# featherwing-interface.net
KiCad netlist of a schematic drawn in EAGLE
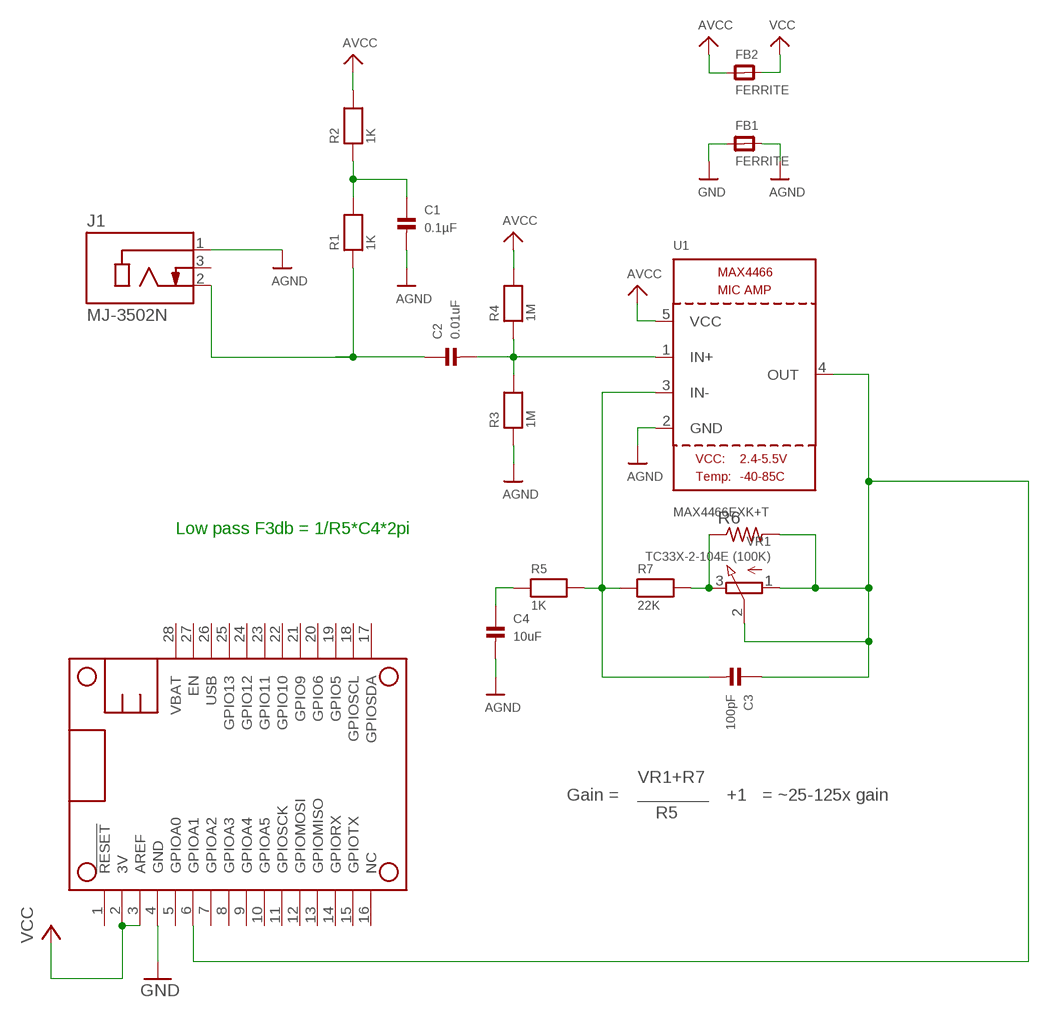
[diagram p0: schematic, sheet 1]

(export (version "E")
  (design (tool "Eeschema 10.0.6"))
  (components
    (comp (ref "C1")
      (value "0.1µF")
      (footprint "eagle-import:0805")
      (libsource (lib "eagle-import") (part "CAP_CERAMIC0805"))
    )
    (comp (ref "C2")
      (value "0.01uF")
      (footprint "eagle-import:0805")
      (libsource (lib "eagle-import") (part "CAP_CERAMIC0805"))
    )
    (comp (ref "C3")
      (value "100pF")
      (footprint "eagle-import:0805")
      (libsource (lib "eagle-import") (part "CAP_CERAMIC0805"))
    )
    (comp (ref "C4")
      (value "10uF")
      (footprint "eagle-import:0805")
      (libsource (lib "eagle-import") (part "CAP_CERAMIC0805"))
    )
    (comp (ref "FB1")
      (value "FERRITE")
      (footprint "eagle-import:0805")
      (libsource (lib "eagle-import") (part "FERRITE0805"))
    )
    (comp (ref "FB2")
      (value "FERRITE")
      (footprint "eagle-import:0805")
      (libsource (lib "eagle-import") (part "FERRITE0805"))
    )
    (comp (ref "J1")
      (value "MJ-3502N")
      (footprint "eagle-import:CUI_MJ-3502N")
      (fields (field (name "MANUFACTURER") "CUI INC"))
      (libsource (lib "eagle-import") (part "MJ-3502N"))
    )
    (comp (ref "MS1")
      (value "FEATHERWING")
      (footprint "eagle-import:FEATHERWING")
      (libsource (lib "eagle-import") (part "FEATHERWING"))
    )
    (comp (ref "R1")
      (value "1K")
      (footprint "eagle-import:0805")
      (libsource (lib "eagle-import") (part "RESISTOR0805"))
    )
    (comp (ref "R2")
      (value "1K")
      (footprint "eagle-import:0805")
      (libsource (lib "eagle-import") (part "RESISTOR0805"))
    )
    (comp (ref "R3")
      (value "1M")
      (footprint "eagle-import:0805")
      (libsource (lib "eagle-import") (part "RESISTOR0805"))
    )
    (comp (ref "R4")
      (value "1M")
      (footprint "eagle-import:0805")
      (libsource (lib "eagle-import") (part "RESISTOR0805"))
    )
    (comp (ref "R5")
      (value "1K")
      (footprint "eagle-import:0805")
      (libsource (lib "eagle-import") (part "RESISTOR0805"))
    )
    (comp (ref "R6")
      (value "R-US_0207/10")
      (footprint "eagle-import:0207_10")
      (libsource (lib "eagle-import") (part "R-US_0207/10"))
    )
    (comp (ref "R7")
      (value "22K")
      (footprint "eagle-import:0805")
      (libsource (lib "eagle-import") (part "RESISTOR0805"))
    )
    (comp (ref "U1")
      (value "MAX4466EXK+T")
      (footprint "eagle-import:SC70-5")
      (libsource (lib "eagle-import") (part "MAX4466{dblquote}{dblquote}"))
    )
    (comp (ref "VR1")
      (value "TC33X-2-104E (100K)")
      (footprint "eagle-import:TRIMPOT_BOURNS_TC33X-2")
      (libsource (lib "eagle-import") (part "TRIMPOTTC33X-2"))
    )
  )
  (nets
    (net (code "1") (name "/USB") (class "Default")
      (node (ref "MS1") (pin "26") (pinfunction "USB_26") (pintype "power_in"))
    )
    (net (code "2") (name "/VBAT") (class "Default")
      (node (ref "MS1") (pin "28") (pinfunction "VBAT_28") (pintype "power_in"))
    )
    (net (code "3") (name "AGND") (class "Default")
      (node (ref "C1") (pin "2") (pinfunction "P$2_2") (pintype "passive"))
      (node (ref "C4") (pin "2") (pinfunction "P$2_2") (pintype "passive"))
      (node (ref "FB1") (pin "2") (pinfunction "P$2_2") (pintype "passive"))
      (node (ref "J1") (pin "1") (pinfunction "1_1") (pintype "passive"))
      (node (ref "R3") (pin "1") (pinfunction "1_1") (pintype "passive"))
      (node (ref "U1") (pin "2") (pinfunction "GND_2") (pintype "bidirectional"))
    )
    (net (code "4") (name "AVCC") (class "Default")
      (node (ref "FB2") (pin "1") (pinfunction "P$1_1") (pintype "passive"))
      (node (ref "R2") (pin "2") (pinfunction "2_2") (pintype "passive"))
      (node (ref "R4") (pin "2") (pinfunction "2_2") (pintype "passive"))
      (node (ref "U1") (pin "5") (pinfunction "VCC_5") (pintype "bidirectional"))
    )
    (net (code "5") (name "GND") (class "Default")
      (node (ref "FB1") (pin "1") (pinfunction "P$1_1") (pintype "passive"))
      (node (ref "MS1") (pin "4") (pinfunction "GND_4") (pintype "power_in"))
    )
    (net (code "6") (name "Net-(C1-P$1)") (class "Default")
      (node (ref "C1") (pin "1") (pinfunction "P$1_1") (pintype "passive"))
      (node (ref "R1") (pin "2") (pinfunction "2_2") (pintype "passive"))
      (node (ref "R2") (pin "1") (pinfunction "1_1") (pintype "passive"))
    )
    (net (code "7") (name "Net-(C2-P$1)") (class "Default")
      (node (ref "C2") (pin "1") (pinfunction "P$1_1") (pintype "passive"))
      (node (ref "J1") (pin "2") (pinfunction "2_2") (pintype "passive"))
      (node (ref "R1") (pin "1") (pinfunction "1_1") (pintype "passive"))
    )
    (net (code "8") (name "Net-(C2-P$2)") (class "Default")
      (node (ref "C2") (pin "2") (pinfunction "P$2_2") (pintype "passive"))
      (node (ref "R3") (pin "2") (pinfunction "2_2") (pintype "passive"))
      (node (ref "R4") (pin "1") (pinfunction "1_1") (pintype "passive"))
      (node (ref "U1") (pin "1") (pinfunction "IN+_1") (pintype "bidirectional"))
    )
    (net (code "9") (name "Net-(C3-P$1)") (class "Default")
      (node (ref "C3") (pin "1") (pinfunction "P$1_1") (pintype "passive"))
      (node (ref "MS1") (pin "6") (pinfunction "GPIOA1_6") (pintype "bidirectional"))
      (node (ref "R6") (pin "2") (pinfunction "2_2") (pintype "passive"))
      (node (ref "U1") (pin "4") (pinfunction "OUT_4") (pintype "bidirectional"))
      (node (ref "VR1") (pin "1") (pinfunction "A_1") (pintype "passive"))
      (node (ref "VR1") (pin "2") (pinfunction "S_2") (pintype "passive"))
    )
    (net (code "10") (name "Net-(C3-P$2)") (class "Default")
      (node (ref "C3") (pin "2") (pinfunction "P$2_2") (pintype "passive"))
      (node (ref "R5") (pin "2") (pinfunction "2_2") (pintype "passive"))
      (node (ref "R7") (pin "1") (pinfunction "1_1") (pintype "passive"))
      (node (ref "U1") (pin "3") (pinfunction "IN-_3") (pintype "bidirectional"))
    )
    (net (code "11") (name "Net-(C4-P$1)") (class "Default")
      (node (ref "C4") (pin "1") (pinfunction "P$1_1") (pintype "passive"))
      (node (ref "R5") (pin "1") (pinfunction "1_1") (pintype "passive"))
    )
    (net (code "12") (name "Net-(VR1-E)") (class "Default")
      (node (ref "R6") (pin "1") (pinfunction "1_1") (pintype "passive"))
      (node (ref "R7") (pin "2") (pinfunction "2_2") (pintype "passive"))
      (node (ref "VR1") (pin "3") (pinfunction "E_3") (pintype "passive"))
    )
    (net (code "13") (name "VCC") (class "Default")
      (node (ref "FB2") (pin "2") (pinfunction "P$2_2") (pintype "passive"))
      (node (ref "MS1") (pin "2") (pinfunction "3V_2") (pintype "power_in"))
      (node (ref "MS1") (pin "3") (pinfunction "AREF_3") (pintype "passive"))
    )
    (net (code "14") (name "unconnected-(J1-Pad3)") (class "Default")
      (node (ref "J1") (pin "3") (pinfunction "3_3") (pintype "passive"))
    )
    (net (code "15") (name "unconnected-(MS1-EN-Pad27)") (class "Default")
      (node (ref "MS1") (pin "27") (pinfunction "EN_27") (pintype "passive"))
    )
    (net (code "16") (name "unconnected-(MS1-GPIO5-Pad19)") (class "Default")
      (node (ref "MS1") (pin "19") (pinfunction "GPIO5_19") (pintype "bidirectional"))
    )
    (net (code "17") (name "unconnected-(MS1-GPIO6-Pad20)") (class "Default")
      (node (ref "MS1") (pin "20") (pinfunction "GPIO6_20") (pintype "bidirectional"))
    )
    (net (code "18") (name "unconnected-(MS1-GPIO9-Pad21)") (class "Default")
      (node (ref "MS1") (pin "21") (pinfunction "GPIO9_21") (pintype "bidirectional"))
    )
    (net (code "19") (name "unconnected-(MS1-GPIO10-Pad22)") (class "Default")
      (node (ref "MS1") (pin "22") (pinfunction "GPIO10_22") (pintype "bidirectional"))
    )
    (net (code "20") (name "unconnected-(MS1-GPIO11-Pad23)") (class "Default")
      (node (ref "MS1") (pin "23") (pinfunction "GPIO11_23") (pintype "bidirectional"))
    )
    (net (code "21") (name "unconnected-(MS1-GPIO12-Pad24)") (class "Default")
      (node (ref "MS1") (pin "24") (pinfunction "GPIO12_24") (pintype "bidirectional"))
    )
    (net (code "22") (name "unconnected-(MS1-GPIO13-Pad25)") (class "Default")
      (node (ref "MS1") (pin "25") (pinfunction "GPIO13_25") (pintype "bidirectional"))
    )
    (net (code "23") (name "unconnected-(MS1-GPIOA0-Pad5)") (class "Default")
      (node (ref "MS1") (pin "5") (pinfunction "GPIOA0_5") (pintype "bidirectional"))
    )
    (net (code "24") (name "unconnected-(MS1-GPIOA2-Pad7)") (class "Default")
      (node (ref "MS1") (pin "7") (pinfunction "GPIOA2_7") (pintype "bidirectional"))
    )
    (net (code "25") (name "unconnected-(MS1-GPIOA3-Pad8)") (class "Default")
      (node (ref "MS1") (pin "8") (pinfunction "GPIOA3_8") (pintype "bidirectional"))
    )
    (net (code "26") (name "unconnected-(MS1-GPIOA4-Pad9)") (class "Default")
      (node (ref "MS1") (pin "9") (pinfunction "GPIOA4_9") (pintype "bidirectional"))
    )
    (net (code "27") (name "unconnected-(MS1-GPIOA5-Pad10)") (class "Default")
      (node (ref "MS1") (pin "10") (pinfunction "GPIOA5_10") (pintype "bidirectional"))
    )
    (net (code "28") (name "unconnected-(MS1-GPIOMISO-Pad13)") (class "Default")
      (node (ref "MS1") (pin "13") (pinfunction "GPIOMISO_13") (pintype "bidirectional"))
    )
    (net (code "29") (name "unconnected-(MS1-GPIOMOSI-Pad12)") (class "Default")
      (node (ref "MS1") (pin "12") (pinfunction "GPIOMOSI_12") (pintype "bidirectional"))
    )
    (net (code "30") (name "unconnected-(MS1-GPIORX-Pad14)") (class "Default")
      (node (ref "MS1") (pin "14") (pinfunction "GPIORX_14") (pintype "bidirectional"))
    )
    (net (code "31") (name "unconnected-(MS1-GPIOSCK-Pad11)") (class "Default")
      (node (ref "MS1") (pin "11") (pinfunction "GPIOSCK_11") (pintype "bidirectional"))
    )
    (net (code "32") (name "unconnected-(MS1-GPIOSCL-Pad18)") (class "Default")
      (node (ref "MS1") (pin "18") (pinfunction "GPIOSCL_18") (pintype "bidirectional"))
    )
    (net (code "33") (name "unconnected-(MS1-GPIOSDA-Pad17)") (class "Default")
      (node (ref "MS1") (pin "17") (pinfunction "GPIOSDA_17") (pintype "bidirectional"))
    )
    (net (code "34") (name "unconnected-(MS1-GPIOTX-Pad15)") (class "Default")
      (node (ref "MS1") (pin "15") (pinfunction "GPIOTX_15") (pintype "bidirectional"))
    )
    (net (code "35") (name "unconnected-(MS1-NC-Pad16)") (class "Default")
      (node (ref "MS1") (pin "16") (pinfunction "NC_16") (pintype "passive"))
    )
    (net (code "36") (name "unconnected-(MS1-~{RESET}-Pad1)") (class "Default")
      (node (ref "MS1") (pin "1") (pinfunction "~{RESET}_1") (pintype "input"))
    )
  )
)
